# lora-slim.net
KiCad netlist of a schematic drawn in EAGLE
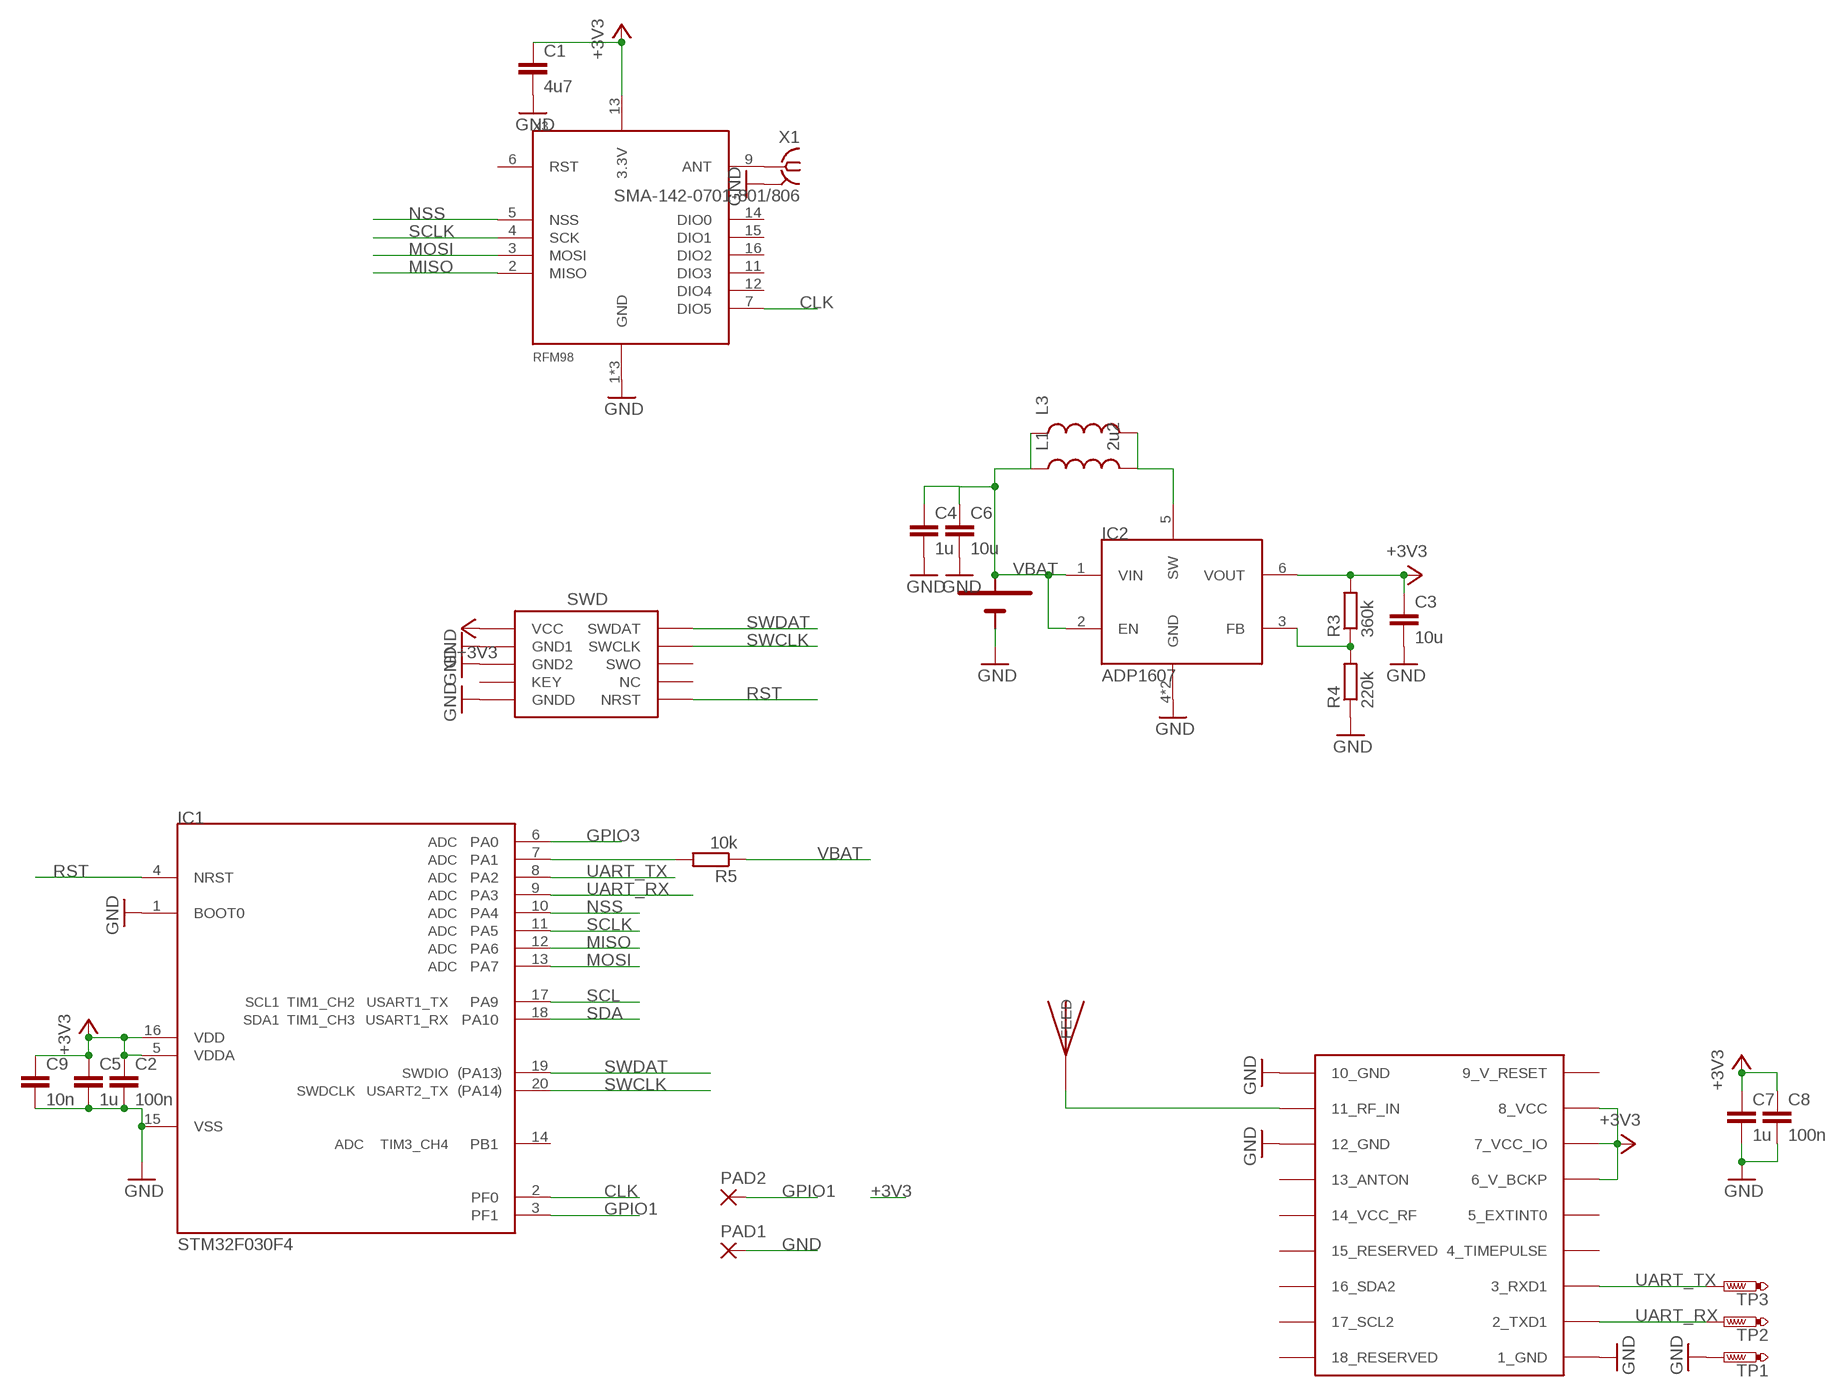
[diagram p0: schematic, sheet 1]

(export (version "E")
  (design (tool "Eeschema 10.0.6"))
  (components
    (comp (ref "C1")
      (value "4u7")
      (footprint "eagle-import:C0603")
      (libsource (lib "eagle-import") (part "C-EUC0603"))
    )
    (comp (ref "C2")
      (value "100n")
      (footprint "eagle-import:C0603")
      (libsource (lib "eagle-import") (part "C-EUC0603"))
    )
    (comp (ref "C3")
      (value "10u")
      (footprint "eagle-import:C0805")
      (libsource (lib "eagle-import") (part "C-EUC0805"))
    )
    (comp (ref "C4")
      (value "1u")
      (footprint "eagle-import:C0603")
      (libsource (lib "eagle-import") (part "C-EUC0603"))
    )
    (comp (ref "C5")
      (value "1u")
      (footprint "eagle-import:C0603")
      (libsource (lib "eagle-import") (part "C-EUC0603"))
    )
    (comp (ref "C6")
      (value "10u")
      (footprint "eagle-import:C0805")
      (libsource (lib "eagle-import") (part "C-EUC0805"))
    )
    (comp (ref "C7")
      (value "1u")
      (footprint "eagle-import:C0603")
      (libsource (lib "eagle-import") (part "C-EUC0603"))
    )
    (comp (ref "C8")
      (value "100n")
      (footprint "eagle-import:C0603")
      (libsource (lib "eagle-import") (part "C-EUC0603"))
    )
    (comp (ref "C9")
      (value "10n")
      (footprint "eagle-import:C0603")
      (libsource (lib "eagle-import") (part "C-EUC0603"))
    )
    (comp (ref "IC1")
      (value "STM32F030F4")
      (footprint "eagle-import:TSSOP20")
      (libsource (lib "eagle-import") (part "STM32F030F4"))
    )
    (comp (ref "IC2")
      (value "ADP1607")
      (footprint "eagle-import:LFCSP6")
      (libsource (lib "eagle-import") (part "ADP1607"))
    )
    (comp (ref "J1")
      (value "SWD_PTH_SHROUD")
      (footprint "eagle-import:SWD_PTH_SHROUD")
      (libsource (lib "eagle-import") (part "SWD_PTH_SHROUD"))
    )
    (comp (ref "L1")
      (value "2u2")
      (footprint "eagle-import:0805")
      (libsource (lib "eagle-import") (part "INDUCTOR0805"))
    )
    (comp (ref "L3")
      (value "INDUCTOR1210")
      (footprint "eagle-import:1210")
      (libsource (lib "eagle-import") (part "INDUCTOR1210"))
    )
    (comp (ref "PAD1")
      (value "2,15/1,0")
      (footprint "eagle-import:2,15_1,0")
      (libsource (lib "eagle-import") (part "2,15/1,0"))
    )
    (comp (ref "PAD2")
      (value "2,15/1,0")
      (footprint "eagle-import:2,15_1,0")
      (libsource (lib "eagle-import") (part "2,15/1,0"))
    )
    (comp (ref "R3")
      (value "360k")
      (footprint "eagle-import:R0603")
      (libsource (lib "eagle-import") (part "R-EU_R0603"))
    )
    (comp (ref "R4")
      (value "220k")
      (footprint "eagle-import:R0603")
      (libsource (lib "eagle-import") (part "R-EU_R0603"))
    )
    (comp (ref "R5")
      (value "10k")
      (footprint "eagle-import:R0603")
      (libsource (lib "eagle-import") (part "R-EU_R0603"))
    )
    (comp (ref "TP1")
      (value "PTR1B1,27")
      (footprint "eagle-import:B1,27")
      (libsource (lib "eagle-import") (part "PTR1B1,27"))
    )
    (comp (ref "TP2")
      (value "PTR1B1,27")
      (footprint "eagle-import:B1,27")
      (libsource (lib "eagle-import") (part "PTR1B1,27"))
    )
    (comp (ref "TP3")
      (value "PTR1B1,27")
      (footprint "eagle-import:B1,27")
      (libsource (lib "eagle-import") (part "PTR1B1,27"))
    )
    (comp (ref "U$5")
      (value "JTI_ANTENNA-1575AT43A40")
      (footprint "eagle-import:JTI_ANTENNA-1575AT43A40")
      (libsource (lib "eagle-import") (part "JTI_ANTENNA-1575AT43A40"))
    )
    (comp (ref "U$6")
      (value "KEYSTONE-53")
      (footprint "eagle-import:KEYSTONE53")
      (libsource (lib "eagle-import") (part "KEYSTONE-53"))
    )
    (comp (ref "X1")
      (value "SMA-142-0701-801/806")
      (footprint "eagle-import:J502-ND-142-0701-801_806")
      (fields (field (name "MF") "JOHNSON COMPONENTS") (field (name "MPN") "142-0701-801"))
      (libsource (lib "eagle-import") (part "SMA-142-0701-801/806"))
    )
    (comp (ref "X2")
      (value "UBLOX_MAX")
      (footprint "eagle-import:UBLOX_MAX")
      (libsource (lib "eagle-import") (part "UBLOX_MAX"))
    )
    (comp (ref "X3")
      (value "RFM98")
      (footprint "eagle-import:RFM97")
      (libsource (lib "eagle-import") (part "RFM98"))
    )
  )
  (nets
    (net (code "1") (name "+3V3") (class "Default")
      (node (ref "C1") (pin "1") (pinfunction "1_1") (pintype "passive"))
      (node (ref "C2") (pin "1") (pinfunction "1_1") (pintype "passive"))
      (node (ref "C3") (pin "1") (pinfunction "1_1") (pintype "passive"))
      (node (ref "C5") (pin "1") (pinfunction "1_1") (pintype "passive"))
      (node (ref "C7") (pin "1") (pinfunction "1_1") (pintype "passive"))
      (node (ref "C8") (pin "1") (pinfunction "1_1") (pintype "passive"))
      (node (ref "C9") (pin "1") (pinfunction "1_1") (pintype "passive"))
      (node (ref "IC1") (pin "16") (pinfunction "VDD_16") (pintype "power_in"))
      (node (ref "IC1") (pin "5") (pinfunction "VDDA_5") (pintype "power_in"))
      (node (ref "IC2") (pin "6") (pinfunction "VOUT_6") (pintype "output"))
      (node (ref "J1") (pin "1") (pinfunction "VCC_1") (pintype "power_in"))
      (node (ref "R3") (pin "2") (pinfunction "2_2") (pintype "passive"))
      (node (ref "X2") (pin "6_V_BCKP") (pinfunction "6_V_BCKP_6_V_BCKP") (pintype "bidirectional"))
      (node (ref "X2") (pin "7_VCC_IO") (pinfunction "7_VCC_IO_7_VCC_IO") (pintype "power_in"))
      (node (ref "X2") (pin "8_VCC") (pinfunction "8_VCC_8_VCC") (pintype "power_in"))
      (node (ref "X3") (pin "13") (pinfunction "3.3V_13") (pintype "power_in"))
    )
    (net (code "2") (name "/9_V_RESET") (class "Default")
      (node (ref "X2") (pin "9_V_RESET") (pinfunction "9_V_RESET_9_V_RESET") (pintype "power_in"))
    )
    (net (code "3") (name "/CLK") (class "Default")
      (node (ref "IC1") (pin "2") (pinfunction "PF0_2") (pintype "bidirectional"))
      (node (ref "X3") (pin "7") (pinfunction "DIO5_7") (pintype "bidirectional"))
    )
    (net (code "4") (name "/GPIO1") (class "Default")
      (node (ref "IC1") (pin "3") (pinfunction "PF1_3") (pintype "bidirectional"))
      (node (ref "PAD2") (pin "1") (pinfunction "P_1") (pintype "passive"))
    )
    (net (code "5") (name "/GPIO3") (class "Default")
      (node (ref "IC1") (pin "6") (pinfunction "PA0_6") (pintype "bidirectional"))
    )
    (net (code "6") (name "/MISO") (class "Default")
      (node (ref "IC1") (pin "12") (pinfunction "PA6_12") (pintype "bidirectional"))
      (node (ref "X3") (pin "2") (pinfunction "MISO_2") (pintype "output"))
    )
    (net (code "7") (name "/MOSI") (class "Default")
      (node (ref "IC1") (pin "13") (pinfunction "PA7_13") (pintype "bidirectional"))
      (node (ref "X3") (pin "3") (pinfunction "MOSI_3") (pintype "input"))
    )
    (net (code "8") (name "/NSS") (class "Default")
      (node (ref "IC1") (pin "10") (pinfunction "PA4_10") (pintype "bidirectional"))
      (node (ref "X3") (pin "5") (pinfunction "NSS_5") (pintype "input"))
    )
    (net (code "9") (name "/RST") (class "Default")
      (node (ref "IC1") (pin "4") (pinfunction "NRST_4") (pintype "input"))
      (node (ref "J1") (pin "10") (pinfunction "NRST_10") (pintype "bidirectional"))
    )
    (net (code "10") (name "/SCL") (class "Default")
      (node (ref "IC1") (pin "17") (pinfunction "PA9_17") (pintype "bidirectional"))
    )
    (net (code "11") (name "/SCLK") (class "Default")
      (node (ref "IC1") (pin "11") (pinfunction "PA5_11") (pintype "bidirectional"))
      (node (ref "X3") (pin "4") (pinfunction "SCK_4") (pintype "input"))
    )
    (net (code "12") (name "/SDA") (class "Default")
      (node (ref "IC1") (pin "18") (pinfunction "PA10_18") (pintype "bidirectional"))
    )
    (net (code "13") (name "/SWCLK") (class "Default")
      (node (ref "IC1") (pin "20") (pinfunction "PA14_20") (pintype "bidirectional"))
      (node (ref "J1") (pin "4") (pinfunction "SWCLK_4") (pintype "bidirectional"))
    )
    (net (code "14") (name "/SWDAT") (class "Default")
      (node (ref "IC1") (pin "19") (pinfunction "PA13_19") (pintype "bidirectional"))
      (node (ref "J1") (pin "2") (pinfunction "SWDAT_2") (pintype "bidirectional"))
    )
    (net (code "15") (name "/UART_RX") (class "Default")
      (node (ref "IC1") (pin "9") (pinfunction "PA3_9") (pintype "bidirectional"))
      (node (ref "TP2") (pin "TP") (pinfunction "TP_TP") (pintype "input"))
      (node (ref "X2") (pin "2_TXD1") (pinfunction "2_TXD1_2_TXD1") (pintype "bidirectional"))
    )
    (net (code "16") (name "/UART_TX") (class "Default")
      (node (ref "IC1") (pin "8") (pinfunction "PA2_8") (pintype "bidirectional"))
      (node (ref "TP3") (pin "TP") (pinfunction "TP_TP") (pintype "input"))
      (node (ref "X2") (pin "3_RXD1") (pinfunction "3_RXD1_3_RXD1") (pintype "bidirectional"))
    )
    (net (code "17") (name "/VBAT") (class "Default")
      (node (ref "C4") (pin "1") (pinfunction "1_1") (pintype "passive"))
      (node (ref "C6") (pin "1") (pinfunction "1_1") (pintype "passive"))
      (node (ref "IC2") (pin "1") (pinfunction "VIN_1") (pintype "input"))
      (node (ref "IC2") (pin "2") (pinfunction "EN_2") (pintype "input"))
      (node (ref "L1") (pin "1") (pinfunction "1_1") (pintype "passive"))
      (node (ref "L3") (pin "1") (pinfunction "1_1") (pintype "passive"))
      (node (ref "R5") (pin "1") (pinfunction "1_1") (pintype "passive"))
      (node (ref "U$6") (pin "P1") (pinfunction "+_P1") (pintype "passive"))
      (node (ref "U$6") (pin "P2") (pinfunction "+_P2") (pintype "passive"))
    )
    (net (code "18") (name "GND") (class "Default")
      (node (ref "C1") (pin "2") (pinfunction "2_2") (pintype "passive"))
      (node (ref "C2") (pin "2") (pinfunction "2_2") (pintype "passive"))
      (node (ref "C3") (pin "2") (pinfunction "2_2") (pintype "passive"))
      (node (ref "C4") (pin "2") (pinfunction "2_2") (pintype "passive"))
      (node (ref "C5") (pin "2") (pinfunction "2_2") (pintype "passive"))
      (node (ref "C6") (pin "2") (pinfunction "2_2") (pintype "passive"))
      (node (ref "C7") (pin "2") (pinfunction "2_2") (pintype "passive"))
      (node (ref "C8") (pin "2") (pinfunction "2_2") (pintype "passive"))
      (node (ref "C9") (pin "2") (pinfunction "2_2") (pintype "passive"))
      (node (ref "IC1") (pin "1") (pinfunction "BOOT0_1") (pintype "input"))
      (node (ref "IC1") (pin "15") (pinfunction "VSS_15") (pintype "power_in"))
      (node (ref "IC2") (pin "4") (pinfunction "GND_4") (pintype "power_in"))
      (node (ref "IC2") (pin "EP") (pinfunction "GND_EP") (pintype "power_in"))
      (node (ref "J1") (pin "3") (pinfunction "GND1_3") (pintype "power_in"))
      (node (ref "J1") (pin "5") (pinfunction "GND2_5") (pintype "power_in"))
      (node (ref "J1") (pin "9") (pinfunction "GNDD_9") (pintype "power_in"))
      (node (ref "PAD1") (pin "1") (pinfunction "P_1") (pintype "passive"))
      (node (ref "R4") (pin "1") (pinfunction "1_1") (pintype "passive"))
      (node (ref "TP1") (pin "TP") (pinfunction "TP_TP") (pintype "input"))
      (node (ref "U$6") (pin "N1") (pinfunction "-_N1") (pintype "passive"))
      (node (ref "U$6") (pin "N2") (pinfunction "-_N2") (pintype "passive"))
      (node (ref "X1") (pin "G@1") (pinfunction "2_G@1") (pintype "passive"))
      (node (ref "X1") (pin "G@2") (pinfunction "2_G@2") (pintype "passive"))
      (node (ref "X1") (pin "G@3") (pinfunction "2_G@3") (pintype "passive"))
      (node (ref "X1") (pin "G@4") (pinfunction "2_G@4") (pintype "passive"))
      (node (ref "X2") (pin "10_GND") (pinfunction "10_GND_10_GND") (pintype "power_in"))
      (node (ref "X2") (pin "12_GND") (pinfunction "12_GND_12_GND") (pintype "power_in"))
      (node (ref "X2") (pin "1_GND") (pinfunction "1_GND_1_GND") (pintype "power_in"))
      (node (ref "X3") (pin "1") (pinfunction "GND_1") (pintype "power_in"))
      (node (ref "X3") (pin "10") (pinfunction "GND_10") (pintype "power_in"))
      (node (ref "X3") (pin "8") (pinfunction "GND_8") (pintype "power_in"))
    )
    (net (code "19") (name "Net-(IC1-PA1)") (class "Default")
      (node (ref "IC1") (pin "7") (pinfunction "PA1_7") (pintype "bidirectional"))
      (node (ref "R5") (pin "2") (pinfunction "2_2") (pintype "passive"))
    )
    (net (code "20") (name "Net-(IC2-FB)") (class "Default")
      (node (ref "IC2") (pin "3") (pinfunction "FB_3") (pintype "input"))
      (node (ref "R3") (pin "1") (pinfunction "1_1") (pintype "passive"))
      (node (ref "R4") (pin "2") (pinfunction "2_2") (pintype "passive"))
    )
    (net (code "21") (name "Net-(IC2-SW)") (class "Default")
      (node (ref "IC2") (pin "5") (pinfunction "SW_5") (pintype "input"))
      (node (ref "L1") (pin "2") (pinfunction "2_2") (pintype "passive"))
      (node (ref "L3") (pin "2") (pinfunction "2_2") (pintype "passive"))
    )
    (net (code "22") (name "Net-(U$5-PadFEED)") (class "Default")
      (node (ref "U$5") (pin "FEED") (pinfunction "FEED_FEED") (pintype "bidirectional"))
      (node (ref "X2") (pin "11_RF_IN") (pinfunction "11_RF_IN_11_RF_IN") (pintype "bidirectional"))
    )
    (net (code "23") (name "Net-(X3-ANT)") (class "Default")
      (node (ref "X1") (pin "1") (pinfunction "1_1") (pintype "passive"))
      (node (ref "X3") (pin "9") (pinfunction "ANT_9") (pintype "bidirectional"))
    )
    (net (code "24") (name "unconnected-(IC1-PB1-Pad14)") (class "Default")
      (node (ref "IC1") (pin "14") (pinfunction "PB1_14") (pintype "bidirectional"))
    )
    (net (code "25") (name "unconnected-(J1-KEY-Pad7)") (class "Default")
      (node (ref "J1") (pin "7") (pinfunction "KEY_7") (pintype "bidirectional"))
    )
    (net (code "26") (name "unconnected-(J1-NC-Pad8)") (class "Default")
      (node (ref "J1") (pin "8") (pinfunction "NC_8") (pintype "no_connect"))
    )
    (net (code "27") (name "unconnected-(J1-SWO-Pad6)") (class "Default")
      (node (ref "J1") (pin "6") (pinfunction "SWO_6") (pintype "bidirectional"))
    )
    (net (code "28") (name "unconnected-(X2-Pad4_TIMEPULSE)") (class "Default")
      (node (ref "X2") (pin "4_TIMEPULSE") (pinfunction "4_TIMEPULSE_4_TIMEPULSE") (pintype "bidirectional"))
    )
    (net (code "29") (name "unconnected-(X2-Pad5_EXTINT0)") (class "Default")
      (node (ref "X2") (pin "5_EXTINT0") (pinfunction "5_EXTINT0_5_EXTINT0") (pintype "bidirectional"))
    )
    (net (code "30") (name "unconnected-(X2-Pad13_ANTON)") (class "Default")
      (node (ref "X2") (pin "13_ANTON") (pinfunction "13_ANTON_13_ANTON") (pintype "bidirectional"))
    )
    (net (code "31") (name "unconnected-(X2-Pad14_VCC_RF)") (class "Default")
      (node (ref "X2") (pin "14_VCC_RF") (pinfunction "14_VCC_RF_14_VCC_RF") (pintype "bidirectional"))
    )
    (net (code "32") (name "unconnected-(X2-Pad15_RESERVED)") (class "Default")
      (node (ref "X2") (pin "15_RESERVED") (pinfunction "15_RESERVED_15_RESERVED") (pintype "bidirectional"))
    )
    (net (code "33") (name "unconnected-(X2-Pad16_SDA2)") (class "Default")
      (node (ref "X2") (pin "16_SDA2") (pinfunction "16_SDA2_16_SDA2") (pintype "bidirectional"))
    )
    (net (code "34") (name "unconnected-(X2-Pad17_SCL2)") (class "Default")
      (node (ref "X2") (pin "17_SCL2") (pinfunction "17_SCL2_17_SCL2") (pintype "bidirectional"))
    )
    (net (code "35") (name "unconnected-(X2-Pad18_RESERVED)") (class "Default")
      (node (ref "X2") (pin "18_RESERVED") (pinfunction "18_RESERVED_18_RESERVED") (pintype "bidirectional"))
    )
    (net (code "36") (name "unconnected-(X3-DIO0-Pad14)") (class "Default")
      (node (ref "X3") (pin "14") (pinfunction "DIO0_14") (pintype "bidirectional"))
    )
    (net (code "37") (name "unconnected-(X3-DIO1-Pad15)") (class "Default")
      (node (ref "X3") (pin "15") (pinfunction "DIO1_15") (pintype "bidirectional"))
    )
    (net (code "38") (name "unconnected-(X3-DIO2-Pad16)") (class "Default")
      (node (ref "X3") (pin "16") (pinfunction "DIO2_16") (pintype "bidirectional"))
    )
    (net (code "39") (name "unconnected-(X3-DIO3-Pad11)") (class "Default")
      (node (ref "X3") (pin "11") (pinfunction "DIO3_11") (pintype "bidirectional"))
    )
    (net (code "40") (name "unconnected-(X3-DIO4-Pad12)") (class "Default")
      (node (ref "X3") (pin "12") (pinfunction "DIO4_12") (pintype "bidirectional"))
    )
    (net (code "41") (name "unconnected-(X3-RST-Pad6)") (class "Default")
      (node (ref "X3") (pin "6") (pinfunction "RST_6") (pintype "input"))
    )
  )
)
